# ATMEGA32u4_Breakout_rev1.net
KiCad netlist of a schematic drawn in EAGLE
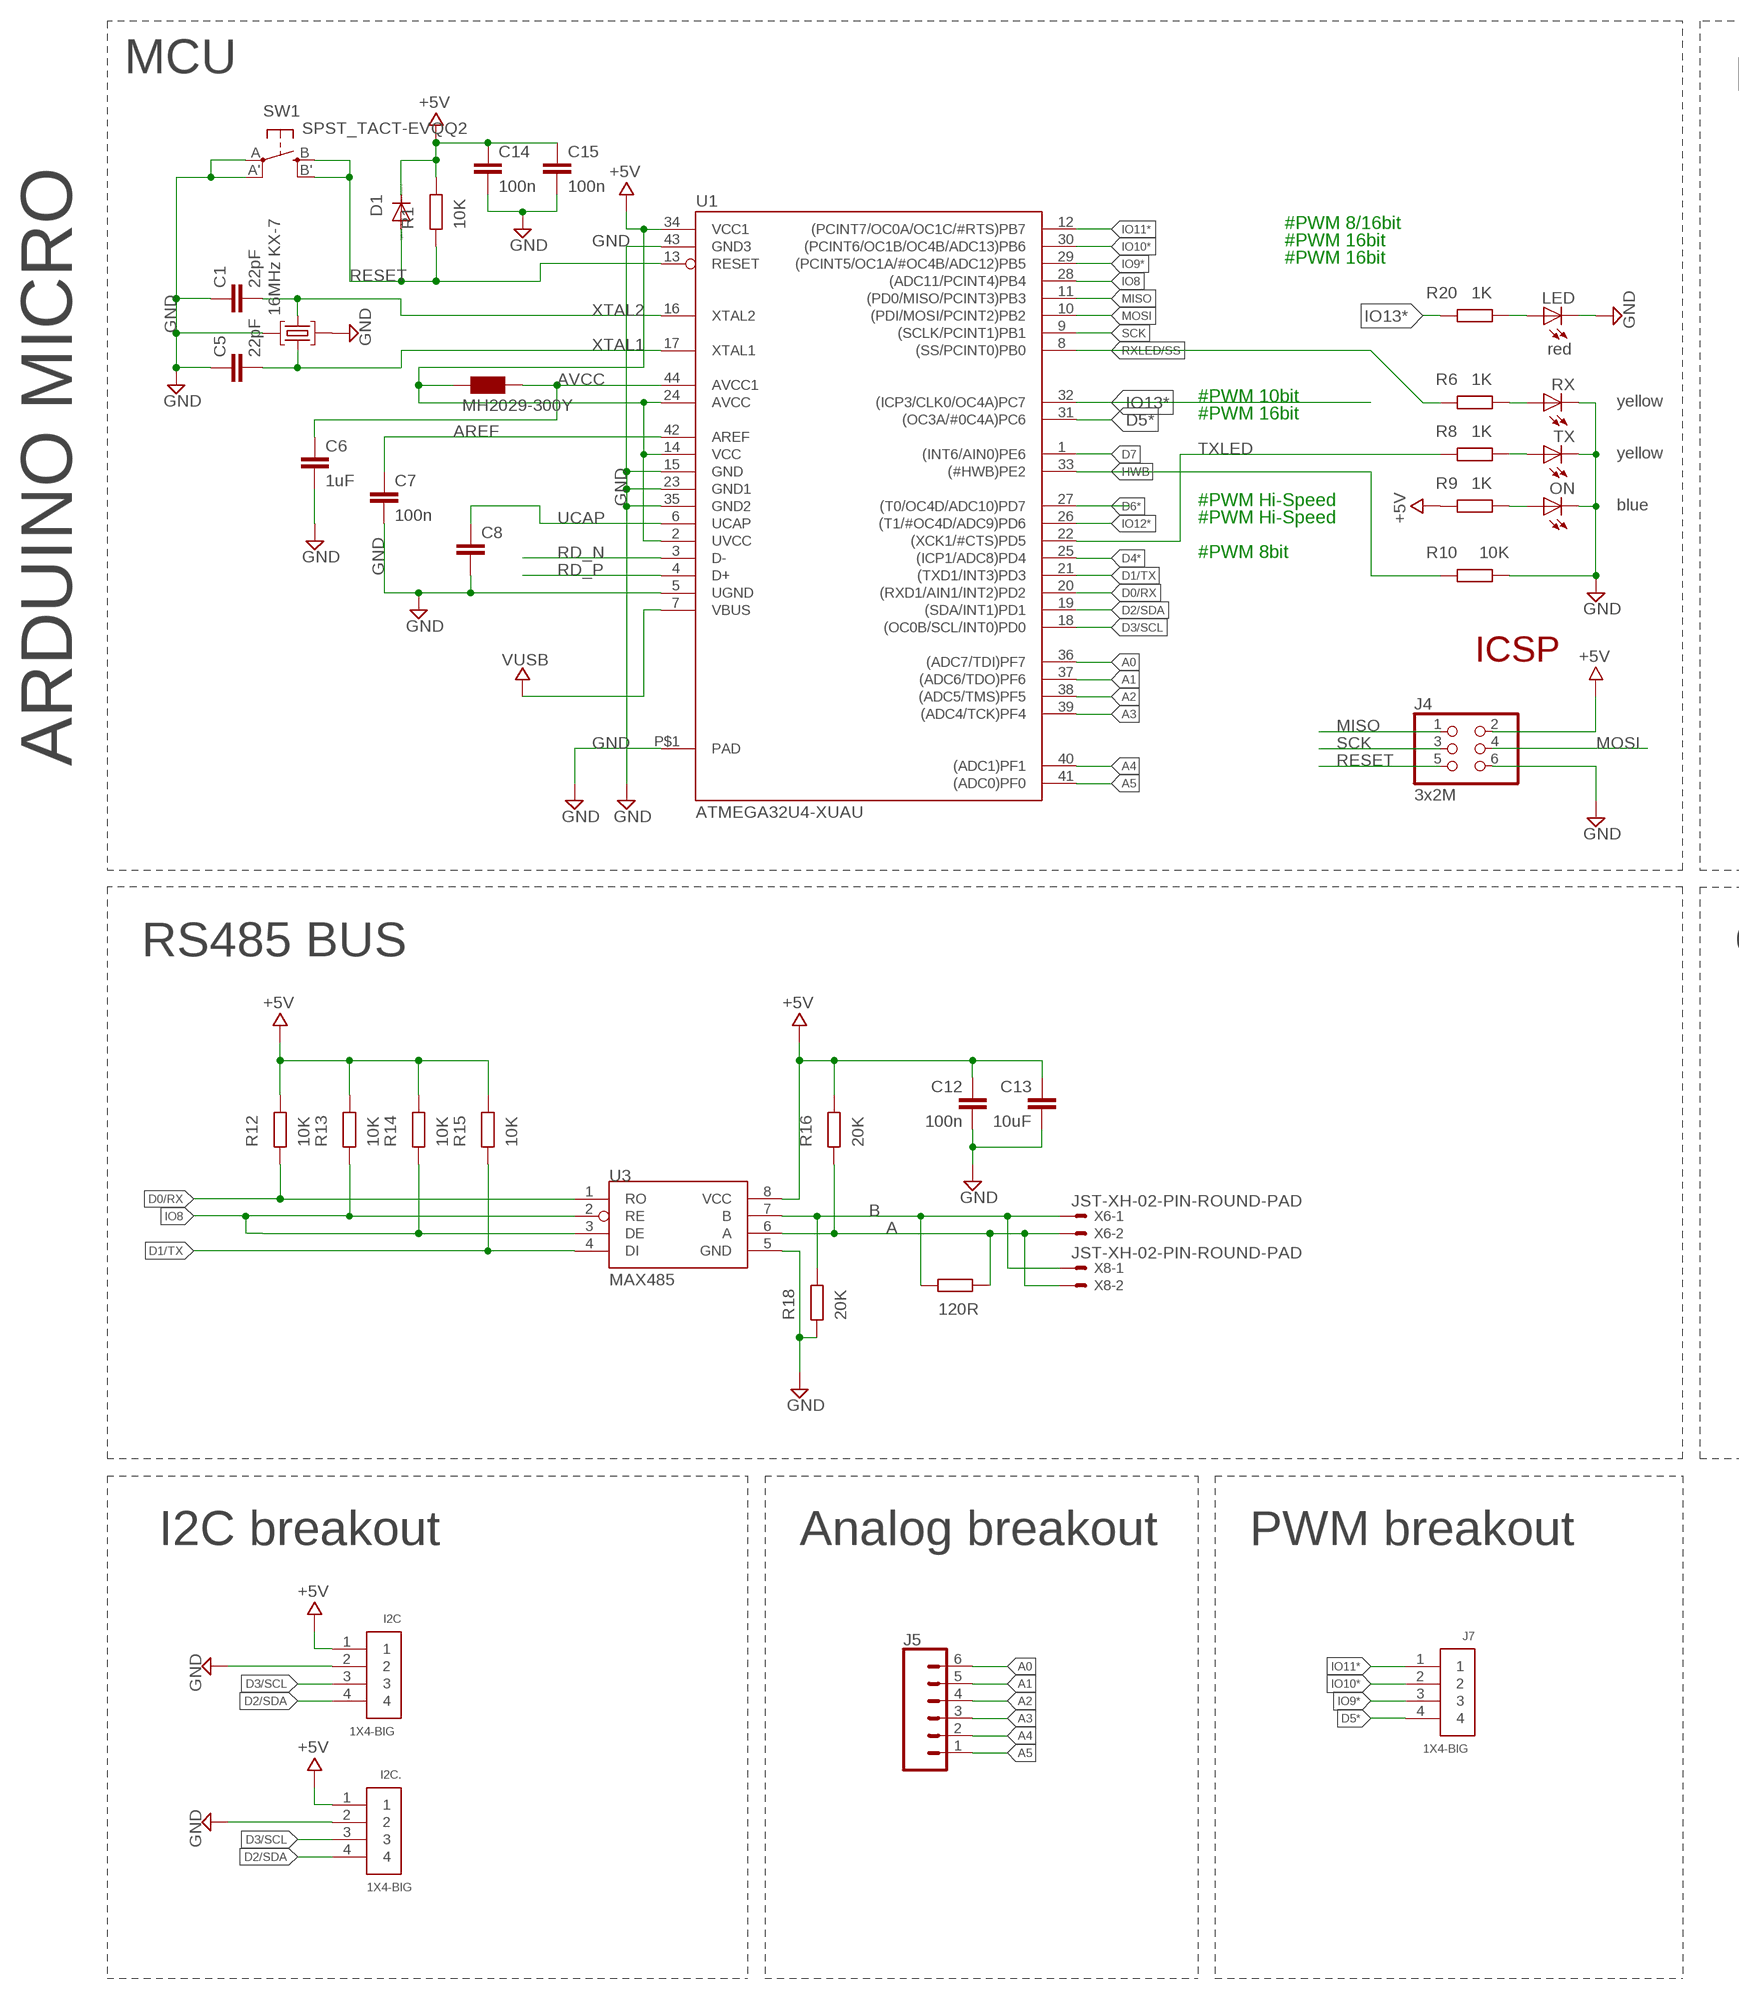
[diagram p0: schematic, sheet 1, part 1 of 2]
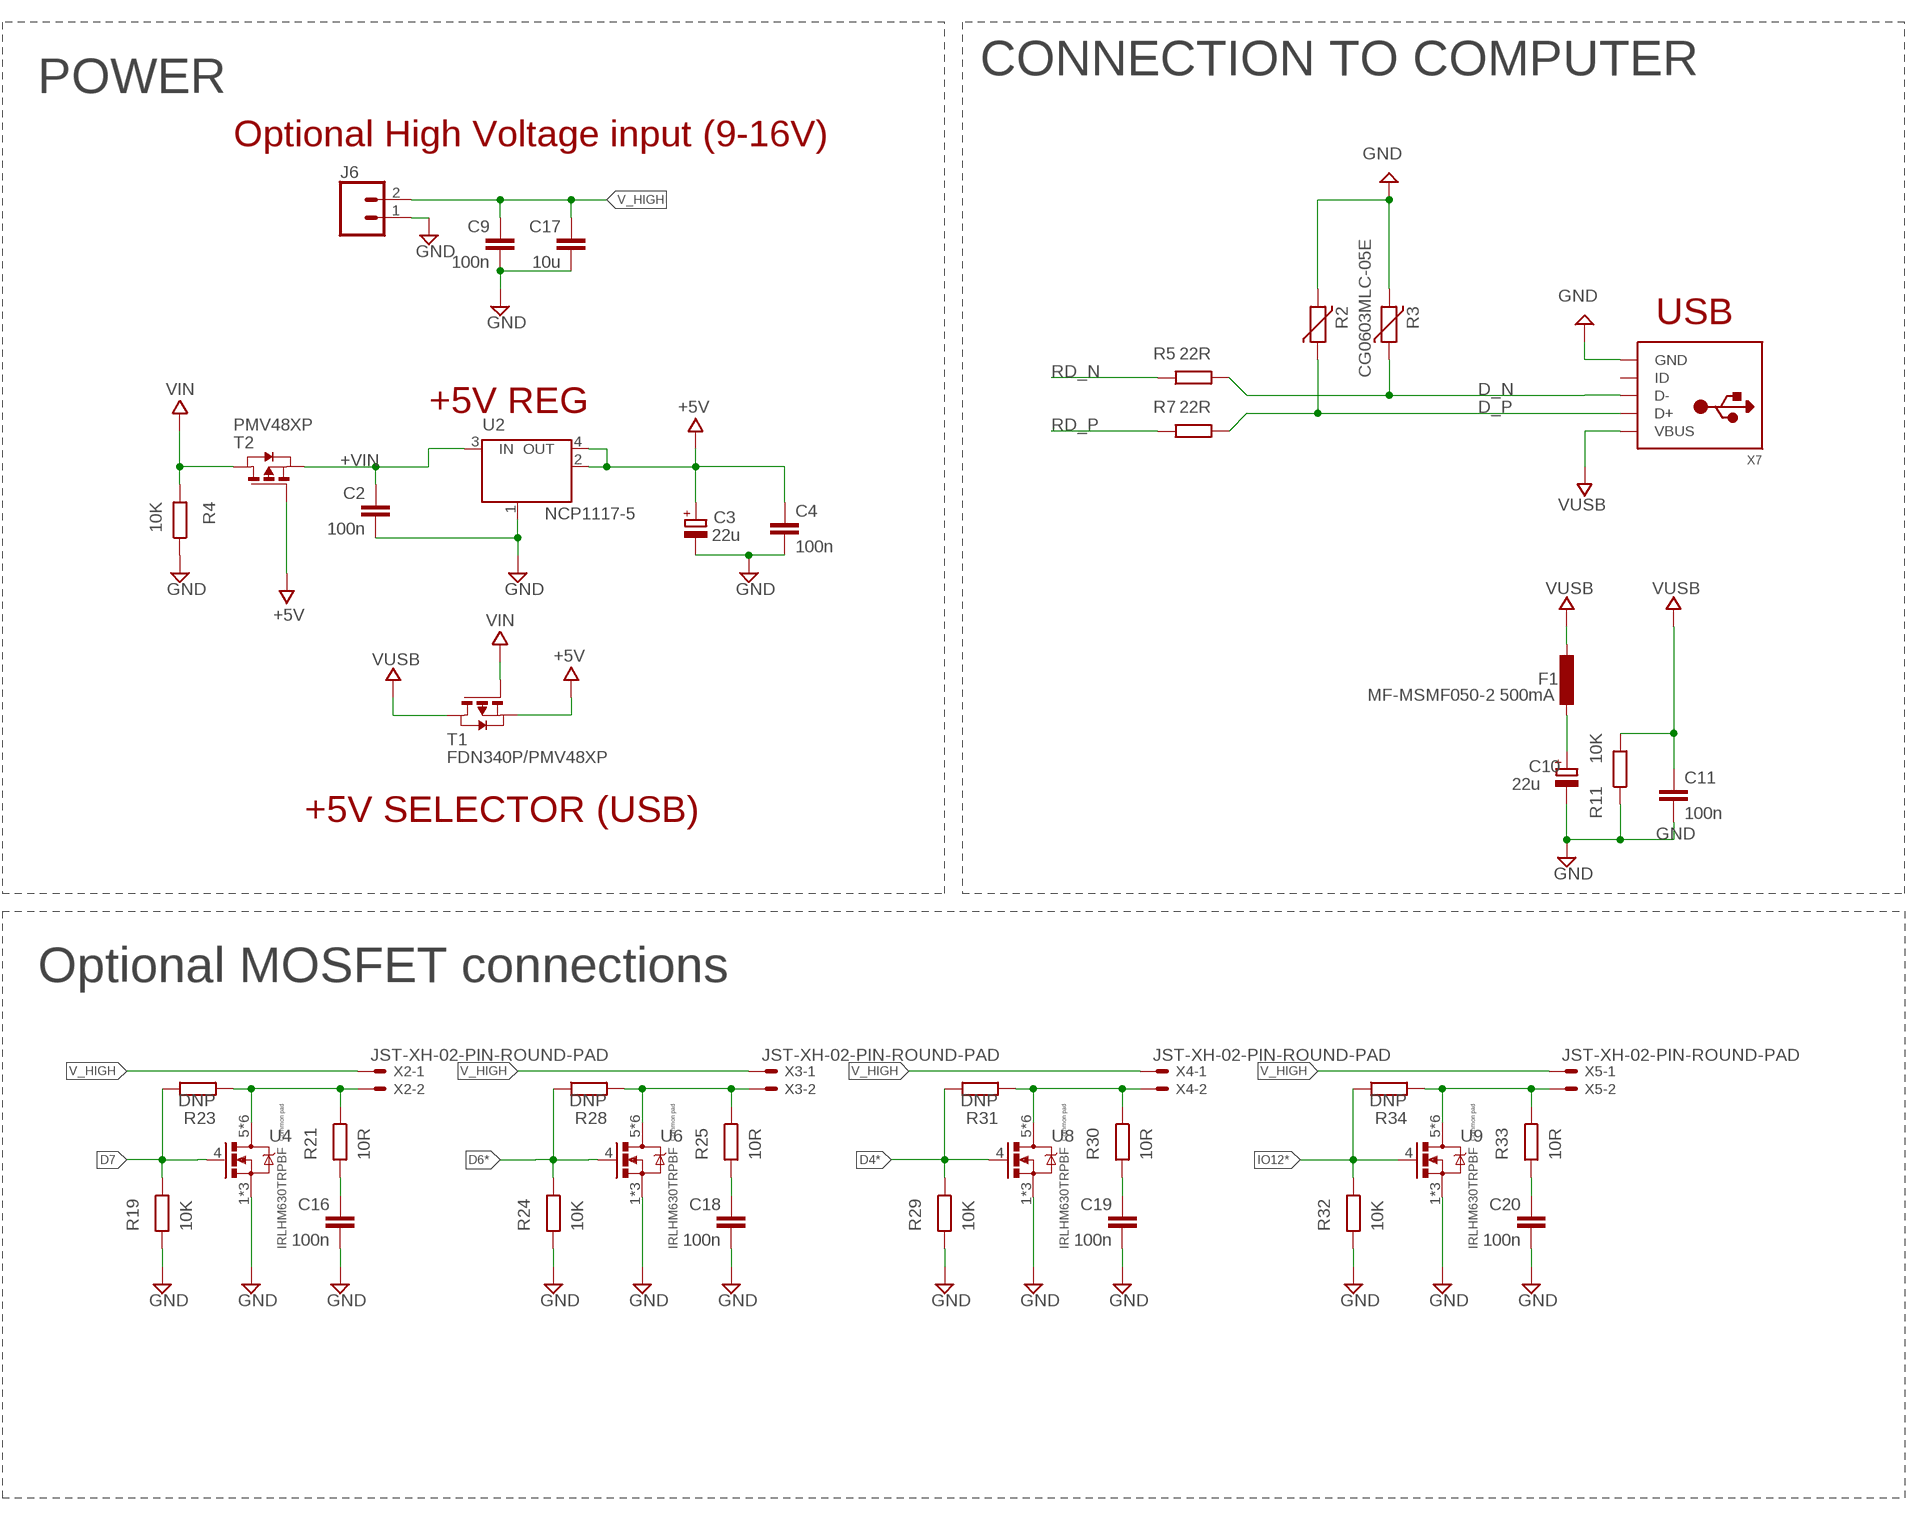
[diagram p1: schematic, sheet 1, part 2 of 2]

(export (version "E")
  (design (tool "Eeschema 10.0.6"))
  (components
    (comp (ref "C1")
      (value "22pF")
      (footprint "eagle-import:C0603-ROUND")
      (libsource (lib "eagle-import") (part "C-EUC0603"))
    )
    (comp (ref "C2")
      (value "100n")
      (footprint "eagle-import:C0603-ROUND")
      (libsource (lib "eagle-import") (part "C-EUC0603"))
    )
    (comp (ref "C3")
      (value "22u")
      (footprint "eagle-import:SMC_B")
      (libsource (lib "eagle-import") (part "CPOL-EUSMCB"))
    )
    (comp (ref "C4")
      (value "100n")
      (footprint "eagle-import:C0603-ROUND")
      (libsource (lib "eagle-import") (part "C-EUC0603"))
    )
    (comp (ref "C5")
      (value "22pF")
      (footprint "eagle-import:C0603-ROUND")
      (libsource (lib "eagle-import") (part "C-EUC0603"))
    )
    (comp (ref "C6")
      (value "1uF")
      (footprint "eagle-import:C0603-ROUND")
      (libsource (lib "eagle-import") (part "C-EUC0603"))
    )
    (comp (ref "C7")
      (value "100n")
      (footprint "eagle-import:C0603-ROUND")
      (libsource (lib "eagle-import") (part "C-EUC0603"))
    )
    (comp (ref "C8")
      (value "1uF")
      (footprint "eagle-import:C0603-ROUND")
      (libsource (lib "eagle-import") (part "C-EUC0603"))
    )
    (comp (ref "C9")
      (value "100n")
      (footprint "eagle-import:C1206")
      (libsource (lib "eagle-import") (part "C-EUC1206"))
    )
    (comp (ref "C10")
      (value "22u")
      (footprint "eagle-import:SMC_B")
      (libsource (lib "eagle-import") (part "CPOL-EUSMCB"))
    )
    (comp (ref "C11")
      (value "100n")
      (footprint "eagle-import:C0603-ROUND")
      (libsource (lib "eagle-import") (part "C-EUC0603"))
    )
    (comp (ref "C12")
      (value "100n")
      (footprint "eagle-import:C0603-ROUND")
      (libsource (lib "eagle-import") (part "C-EUC0603"))
    )
    (comp (ref "C13")
      (value "10uF")
      (footprint "eagle-import:C0603-ROUND")
      (libsource (lib "eagle-import") (part "C-EUC0603"))
    )
    (comp (ref "C14")
      (value "100n")
      (footprint "eagle-import:C0603-ROUND")
      (libsource (lib "eagle-import") (part "C-EUC0603"))
    )
    (comp (ref "C15")
      (value "100n")
      (footprint "eagle-import:C0603-ROUND")
      (libsource (lib "eagle-import") (part "C-EUC0603"))
    )
    (comp (ref "C16")
      (value "100n")
      (footprint "eagle-import:C0603-ROUND")
      (libsource (lib "eagle-import") (part "C-EUC0603"))
    )
    (comp (ref "C17")
      (value "10u")
      (footprint "eagle-import:C1206")
      (libsource (lib "eagle-import") (part "C-EUC1206"))
    )
    (comp (ref "C18")
      (value "100n")
      (footprint "eagle-import:C0603-ROUND")
      (libsource (lib "eagle-import") (part "C-EUC0603"))
    )
    (comp (ref "C19")
      (value "100n")
      (footprint "eagle-import:C0603-ROUND")
      (libsource (lib "eagle-import") (part "C-EUC0603"))
    )
    (comp (ref "C20")
      (value "100n")
      (footprint "eagle-import:C0603-ROUND")
      (libsource (lib "eagle-import") (part "C-EUC0603"))
    )
    (comp (ref "D1")
      (value "CD1206-S01575")
      (footprint "eagle-import:MINIMELF")
      (libsource (lib "eagle-import") (part "DIODE-MINIMELF"))
    )
    (comp (ref "F1")
      (value "MF-MSMF050-2 500mA")
      (footprint "eagle-import:L1812")
      (libsource (lib "eagle-import") (part "L-EUL1812"))
    )
    (comp (ref "I2C")
      (value "1X4-BIG")
      (footprint "eagle-import:1X04-BIG")
      (libsource (lib "eagle-import") (part "1X4-BIG"))
    )
    (comp (ref "I2C.")
      (value "1X4-BIG")
      (footprint "eagle-import:1X04-BIG")
      (libsource (lib "eagle-import") (part "1X4-BIG"))
    )
    (comp (ref "J4")
      (value "3x2M")
      (footprint "eagle-import:2X03")
      (libsource (lib "eagle-import") (part "PINHD-2X3"))
    )
    (comp (ref "J5")
      (value "CONN_06SILK_FEMALE_PTH")
      (footprint "eagle-import:1X06")
      (libsource (lib "eagle-import") (part "CONN_06SILK_FEMALE_PTH"))
    )
    (comp (ref "J6")
      (value "CONN_023.5MM")
      (footprint "eagle-import:SCREWTERMINAL-3.5MM-2")
      (libsource (lib "eagle-import") (part "CONN_023.5MM"))
    )
    (comp (ref "J7")
      (value "1X4-BIG")
      (footprint "eagle-import:1X04-BIG")
      (libsource (lib "eagle-import") (part "1X4-BIG"))
    )
    (comp (ref "L2")
      (value "MH2029-300Y")
      (footprint "eagle-import:0805")
      (libsource (lib "eagle-import") (part "WE-CBF_0805"))
    )
    (comp (ref "LED")
      (value "red")
      (footprint "eagle-import:CHIPLED_0805")
      (libsource (lib "eagle-import") (part "LEDCHIPLED_0805"))
    )
    (comp (ref "ON")
      (value "blue")
      (footprint "eagle-import:CHIPLED_0805")
      (libsource (lib "eagle-import") (part "LEDCHIPLED_0805"))
    )
    (comp (ref "R1")
      (value "10K")
      (footprint "eagle-import:R0603-ROUND")
      (libsource (lib "eagle-import") (part "R-EU_R0603"))
    )
    (comp (ref "R2")
      (value "CG0603MLC-05E")
      (footprint "eagle-import:CT_CN0603")
      (libsource (lib "eagle-import") (part "VARISTORCN0603"))
    )
    (comp (ref "R3")
      (value "CG0603MLC-05E")
      (footprint "eagle-import:CT_CN0603")
      (libsource (lib "eagle-import") (part "VARISTORCN0603"))
    )
    (comp (ref "R4")
      (value "10K")
      (footprint "eagle-import:R0603-ROUND")
      (libsource (lib "eagle-import") (part "R-EU_R0603"))
    )
    (comp (ref "R5")
      (value "22R")
      (footprint "eagle-import:R0603-ROUND")
      (libsource (lib "eagle-import") (part "R-EU_R0603"))
    )
    (comp (ref "R6")
      (value "1K")
      (footprint "eagle-import:R0603-ROUND")
      (libsource (lib "eagle-import") (part "R-EU_R0603"))
    )
    (comp (ref "R7")
      (value "22R")
      (footprint "eagle-import:R0603-ROUND")
      (libsource (lib "eagle-import") (part "R-EU_R0603"))
    )
    (comp (ref "R8")
      (value "1K")
      (footprint "eagle-import:R0603-ROUND")
      (libsource (lib "eagle-import") (part "R-EU_R0603"))
    )
    (comp (ref "R9")
      (value "1K")
      (footprint "eagle-import:R0603-ROUND")
      (libsource (lib "eagle-import") (part "R-EU_R0603"))
    )
    (comp (ref "R10")
      (value "10K")
      (footprint "eagle-import:R0603-ROUND")
      (libsource (lib "eagle-import") (part "R-EU_R0603"))
    )
    (comp (ref "R11")
      (value "10K")
      (footprint "eagle-import:R0603-ROUND")
      (libsource (lib "eagle-import") (part "R-EU_R0603"))
    )
    (comp (ref "R12")
      (value "10K")
      (footprint "eagle-import:R0603-ROUND")
      (libsource (lib "eagle-import") (part "R-EU_R0603"))
    )
    (comp (ref "R13")
      (value "10K")
      (footprint "eagle-import:R0603-ROUND")
      (libsource (lib "eagle-import") (part "R-EU_R0603"))
    )
    (comp (ref "R14")
      (value "10K")
      (footprint "eagle-import:R0603-ROUND")
      (libsource (lib "eagle-import") (part "R-EU_R0603"))
    )
    (comp (ref "R15")
      (value "10K")
      (footprint "eagle-import:R0603-ROUND")
      (libsource (lib "eagle-import") (part "R-EU_R0603"))
    )
    (comp (ref "R16")
      (value "20K")
      (footprint "eagle-import:R0603-ROUND")
      (libsource (lib "eagle-import") (part "R-EU_R0603"))
    )
    (comp (ref "R17")
      (value "120R")
      (footprint "eagle-import:R0603-ROUND")
      (libsource (lib "eagle-import") (part "R-EU_R0603"))
    )
    (comp (ref "R18")
      (value "20K")
      (footprint "eagle-import:R0603-ROUND")
      (libsource (lib "eagle-import") (part "R-EU_R0603"))
    )
    (comp (ref "R19")
      (value "10K")
      (footprint "eagle-import:R0603-ROUND")
      (libsource (lib "eagle-import") (part "R-EU_R0603"))
    )
    (comp (ref "R20")
      (value "1K")
      (footprint "eagle-import:R0603-ROUND")
      (libsource (lib "eagle-import") (part "R-EU_R0603"))
    )
    (comp (ref "R21")
      (value "10R")
      (footprint "eagle-import:R0603-ROUND")
      (libsource (lib "eagle-import") (part "R-EU_R0603"))
    )
    (comp (ref "R23")
      (value "DNP")
      (footprint "eagle-import:R0603-ROUND")
      (libsource (lib "eagle-import") (part "R-EU_R0603"))
    )
    (comp (ref "R24")
      (value "10K")
      (footprint "eagle-import:R0603-ROUND")
      (libsource (lib "eagle-import") (part "R-EU_R0603"))
    )
    (comp (ref "R25")
      (value "10R")
      (footprint "eagle-import:R0603-ROUND")
      (libsource (lib "eagle-import") (part "R-EU_R0603"))
    )
    (comp (ref "R28")
      (value "DNP")
      (footprint "eagle-import:R0603-ROUND")
      (libsource (lib "eagle-import") (part "R-EU_R0603"))
    )
    (comp (ref "R29")
      (value "10K")
      (footprint "eagle-import:R0603-ROUND")
      (libsource (lib "eagle-import") (part "R-EU_R0603"))
    )
    (comp (ref "R30")
      (value "10R")
      (footprint "eagle-import:R0603-ROUND")
      (libsource (lib "eagle-import") (part "R-EU_R0603"))
    )
    (comp (ref "R31")
      (value "DNP")
      (footprint "eagle-import:R0603-ROUND")
      (libsource (lib "eagle-import") (part "R-EU_R0603"))
    )
    (comp (ref "R32")
      (value "10K")
      (footprint "eagle-import:R0603-ROUND")
      (libsource (lib "eagle-import") (part "R-EU_R0603"))
    )
    (comp (ref "R33")
      (value "10R")
      (footprint "eagle-import:R0603-ROUND")
      (libsource (lib "eagle-import") (part "R-EU_R0603"))
    )
    (comp (ref "R34")
      (value "DNP")
      (footprint "eagle-import:R0603-ROUND")
      (libsource (lib "eagle-import") (part "R-EU_R0603"))
    )
    (comp (ref "RX")
      (value "yellow")
      (footprint "eagle-import:CHIPLED_0805")
      (libsource (lib "eagle-import") (part "LEDCHIPLED_0805"))
    )
    (comp (ref "SW1")
      (value "SPST_TACT-EVQQ2")
      (footprint "eagle-import:EVQ-Q2")
      (libsource (lib "eagle-import") (part "SPST_TACT-EVQQ2"))
    )
    (comp (ref "T1")
      (value "FDN340P/PMV48XP")
      (footprint "eagle-import:SOT-23")
      (libsource (lib "eagle-import") (part "PMOSSOT23"))
    )
    (comp (ref "T2")
      (value "PMV48XP")
      (footprint "eagle-import:SOT-23")
      (libsource (lib "eagle-import") (part "PMOSSOT23"))
    )
    (comp (ref "TX")
      (value "yellow")
      (footprint "eagle-import:CHIPLED_0805")
      (libsource (lib "eagle-import") (part "LEDCHIPLED_0805"))
    )
    (comp (ref "U1")
      (value "ATMEGA32U4-XUAU")
      (footprint "eagle-import:TQFP44-PAD")
      (libsource (lib "eagle-import") (part "ATMEGA32U4-XUAU"))
    )
    (comp (ref "U2")
      (value "NCP1117-5")
      (footprint "eagle-import:SOT223")
      (libsource (lib "eagle-import") (part "LINEAR_MC33269ST"))
    )
    (comp (ref "U3")
      (value "MAX485")
      (footprint "eagle-import:SO08")
      (fields (field (name "MF") "Maxim Integrated"))
      (libsource (lib "eagle-import") (part "MAX485"))
    )
    (comp (ref "U4")
      (value "IRLHM630TRPBF")
      (footprint "eagle-import:IRLHM630TRPBF")
      (libsource (lib "eagle-import") (part "IRLHM630TRPBF"))
    )
    (comp (ref "U6")
      (value "IRLHM630TRPBF")
      (footprint "eagle-import:IRLHM630TRPBF")
      (libsource (lib "eagle-import") (part "IRLHM630TRPBF"))
    )
    (comp (ref "U8")
      (value "IRLHM630TRPBF")
      (footprint "eagle-import:IRLHM630TRPBF")
      (libsource (lib "eagle-import") (part "IRLHM630TRPBF"))
    )
    (comp (ref "U9")
      (value "IRLHM630TRPBF")
      (footprint "eagle-import:IRLHM630TRPBF")
      (libsource (lib "eagle-import") (part "IRLHM630TRPBF"))
    )
    (comp (ref "X1")
      (value "16MHz KX-7")
      (footprint "eagle-import:CRYSTAL-3.2-2.5")
      (libsource (lib "eagle-import") (part "CRYSTAL-3.2-2.5"))
    )
    (comp (ref "X2")
      (value "JST-XH-02-PIN-ROUND-PAD")
      (footprint "eagle-import:JST-XH-02-PACKAGE-ROUND-PAD")
      (libsource (lib "eagle-import") (part "JST-XH-02-PIN-ROUND-PAD"))
    )
    (comp (ref "X3")
      (value "JST-XH-02-PIN-ROUND-PAD")
      (footprint "eagle-import:JST-XH-02-PACKAGE-ROUND-PAD")
      (libsource (lib "eagle-import") (part "JST-XH-02-PIN-ROUND-PAD"))
    )
    (comp (ref "X4")
      (value "JST-XH-02-PIN-ROUND-PAD")
      (footprint "eagle-import:JST-XH-02-PACKAGE-ROUND-PAD")
      (libsource (lib "eagle-import") (part "JST-XH-02-PIN-ROUND-PAD"))
    )
    (comp (ref "X5")
      (value "JST-XH-02-PIN-ROUND-PAD")
      (footprint "eagle-import:JST-XH-02-PACKAGE-ROUND-PAD")
      (libsource (lib "eagle-import") (part "JST-XH-02-PIN-ROUND-PAD"))
    )
    (comp (ref "X6")
      (value "JST-XH-02-PIN-ROUND-PAD")
      (footprint "eagle-import:JST-XH-02-PACKAGE-ROUND-PAD")
      (libsource (lib "eagle-import") (part "JST-XH-02-PIN-ROUND-PAD"))
    )
    (comp (ref "X7")
      (value "MICROBUILDER_USB_MICRO_20329_V2")
      (footprint "eagle-import:MICROBUILDER_4UCONN_20329_V2")
      (libsource (lib "eagle-import") (part "MICROBUILDER_USB_MICRO_20329_V2"))
    )
    (comp (ref "X8")
      (value "JST-XH-02-PIN-ROUND-PAD")
      (footprint "eagle-import:JST-XH-02-PACKAGE-ROUND-PAD")
      (libsource (lib "eagle-import") (part "JST-XH-02-PIN-ROUND-PAD"))
    )
  )
  (nets
    (net (code "1") (name "+5V") (class "Default")
      (node (ref "C12") (pin "1") (pinfunction "1_1") (pintype "passive"))
      (node (ref "C13") (pin "1") (pinfunction "1_1") (pintype "passive"))
      (node (ref "C14") (pin "1") (pinfunction "1_1") (pintype "passive"))
      (node (ref "C15") (pin "1") (pinfunction "1_1") (pintype "passive"))
      (node (ref "C3") (pin "+") (pinfunction "+_+") (pintype "passive"))
      (node (ref "C4") (pin "1") (pinfunction "1_1") (pintype "passive"))
      (node (ref "D1") (pin "C") (pinfunction "C_C") (pintype "passive"))
      (node (ref "I2C") (pin "1") (pinfunction "1_1") (pintype "bidirectional"))
      (node (ref "I2C.") (pin "1") (pinfunction "1_1") (pintype "bidirectional"))
      (node (ref "J4") (pin "2") (pinfunction "2_2") (pintype "passive"))
      (node (ref "L2") (pin "1") (pinfunction "1_1") (pintype "passive"))
      (node (ref "R1") (pin "1") (pinfunction "1_1") (pintype "passive"))
      (node (ref "R12") (pin "1") (pinfunction "1_1") (pintype "passive"))
      (node (ref "R13") (pin "1") (pinfunction "1_1") (pintype "passive"))
      (node (ref "R14") (pin "1") (pinfunction "1_1") (pintype "passive"))
      (node (ref "R15") (pin "1") (pinfunction "1_1") (pintype "passive"))
      (node (ref "R16") (pin "1") (pinfunction "1_1") (pintype "passive"))
      (node (ref "R9") (pin "1") (pinfunction "1_1") (pintype "passive"))
      (node (ref "T1") (pin "2") (pinfunction "S_2") (pintype "passive"))
      (node (ref "T2") (pin "3") (pinfunction "G_3") (pintype "passive"))
      (node (ref "U1") (pin "14") (pinfunction "VCC_14") (pintype "power_in"))
      (node (ref "U1") (pin "2") (pinfunction "UVCC_2") (pintype "power_in"))
      (node (ref "U1") (pin "24") (pinfunction "AVCC_24") (pintype "power_in"))
      (node (ref "U1") (pin "34") (pinfunction "VCC1_34") (pintype "power_in"))
      (node (ref "U2") (pin "2") (pinfunction "OUT_2") (pintype "passive"))
      (node (ref "U2") (pin "4") (pinfunction "OUT_4") (pintype "passive"))
      (node (ref "U3") (pin "8") (pinfunction "VCC_8") (pintype "bidirectional"))
    )
    (net (code "2") (name "/+VIN") (class "Default")
      (node (ref "C2") (pin "1") (pinfunction "1_1") (pintype "passive"))
      (node (ref "T2") (pin "2") (pinfunction "S_2") (pintype "passive"))
      (node (ref "U2") (pin "3") (pinfunction "IN_3") (pintype "input"))
    )
    (net (code "3") (name "/A") (class "Default")
      (node (ref "R16") (pin "2") (pinfunction "2_2") (pintype "passive"))
      (node (ref "R17") (pin "1") (pinfunction "1_1") (pintype "passive"))
      (node (ref "U3") (pin "6") (pinfunction "A_6") (pintype "bidirectional"))
      (node (ref "X6") (pin "2") (pinfunction "S_2") (pintype "passive"))
      (node (ref "X8") (pin "2") (pinfunction "S_2") (pintype "passive"))
    )
    (net (code "4") (name "/AREF") (class "Default")
      (node (ref "C7") (pin "1") (pinfunction "1_1") (pintype "passive"))
      (node (ref "U1") (pin "42") (pinfunction "AREF_42") (pintype "power_in"))
    )
    (net (code "5") (name "/AVCC") (class "Default")
      (node (ref "C6") (pin "1") (pinfunction "1_1") (pintype "passive"))
      (node (ref "L2") (pin "2") (pinfunction "2_2") (pintype "passive"))
      (node (ref "U1") (pin "44") (pinfunction "AVCC1_44") (pintype "power_in"))
    )
    (net (code "6") (name "/B") (class "Default")
      (node (ref "R17") (pin "2") (pinfunction "2_2") (pintype "passive"))
      (node (ref "R18") (pin "1") (pinfunction "1_1") (pintype "passive"))
      (node (ref "U3") (pin "7") (pinfunction "B_7") (pintype "bidirectional"))
      (node (ref "X6") (pin "1") (pinfunction "S_1") (pintype "passive"))
      (node (ref "X8") (pin "1") (pinfunction "S_1") (pintype "passive"))
    )
    (net (code "7") (name "/D_N") (class "Default")
      (node (ref "R3") (pin "1") (pinfunction "1_1") (pintype "passive"))
      (node (ref "R5") (pin "2") (pinfunction "2_2") (pintype "passive"))
      (node (ref "X7") (pin "D-") (pinfunction "D-_D-") (pintype "bidirectional"))
    )
    (net (code "8") (name "/D_P") (class "Default")
      (node (ref "R2") (pin "1") (pinfunction "1_1") (pintype "passive"))
      (node (ref "R7") (pin "2") (pinfunction "2_2") (pintype "passive"))
      (node (ref "X7") (pin "D+") (pinfunction "D+_D+") (pintype "bidirectional"))
    )
    (net (code "9") (name "/RD_N") (class "Default")
      (node (ref "R5") (pin "1") (pinfunction "1_1") (pintype "passive"))
      (node (ref "U1") (pin "3") (pinfunction "D-_3") (pintype "bidirectional"))
    )
    (net (code "10") (name "/RD_P") (class "Default")
      (node (ref "R7") (pin "1") (pinfunction "1_1") (pintype "passive"))
      (node (ref "U1") (pin "4") (pinfunction "D+_4") (pintype "bidirectional"))
    )
    (net (code "11") (name "/RESET") (class "Default")
      (node (ref "D1") (pin "A") (pinfunction "A_A") (pintype "passive"))
      (node (ref "J4") (pin "5") (pinfunction "5_5") (pintype "passive"))
      (node (ref "R1") (pin "2") (pinfunction "2_2") (pintype "passive"))
      (node (ref "SW1") (pin "B") (pinfunction "S_B") (pintype "passive"))
      (node (ref "SW1") (pin "B'") (pinfunction "S1_B'") (pintype "passive"))
      (node (ref "U1") (pin "13") (pinfunction "RESET_13") (pintype "input"))
    )
    (net (code "12") (name "/TXLED") (class "Default")
      (node (ref "R8") (pin "1") (pinfunction "1_1") (pintype "passive"))
      (node (ref "U1") (pin "22") (pinfunction "(XCK1/#CTS)PD5_22") (pintype "bidirectional"))
    )
    (net (code "13") (name "/UCAP") (class "Default")
      (node (ref "C8") (pin "1") (pinfunction "1_1") (pintype "passive"))
      (node (ref "U1") (pin "6") (pinfunction "UCAP_6") (pintype "passive"))
    )
    (net (code "14") (name "/XTAL1") (class "Default")
      (node (ref "C5") (pin "2") (pinfunction "2_2") (pintype "passive"))
      (node (ref "U1") (pin "17") (pinfunction "XTAL1_17") (pintype "bidirectional"))
      (node (ref "X1") (pin "3") (pinfunction "C2_3") (pintype "passive"))
    )
    (net (code "15") (name "/XTAL2") (class "Default")
      (node (ref "C1") (pin "2") (pinfunction "2_2") (pintype "passive"))
      (node (ref "U1") (pin "16") (pinfunction "XTAL2_16") (pintype "bidirectional"))
      (node (ref "X1") (pin "1") (pinfunction "C1_1") (pintype "passive"))
    )
    (net (code "16") (name "A0") (class "Default")
      (node (ref "J5") (pin "6") (pinfunction "6_6") (pintype "passive"))
      (node (ref "U1") (pin "36") (pinfunction "(ADC7/TDI)PF7_36") (pintype "bidirectional"))
    )
    (net (code "17") (name "A1") (class "Default")
      (node (ref "J5") (pin "5") (pinfunction "5_5") (pintype "passive"))
      (node (ref "U1") (pin "37") (pinfunction "(ADC6/TDO)PF6_37") (pintype "bidirectional"))
    )
    (net (code "18") (name "A2") (class "Default")
      (node (ref "J5") (pin "4") (pinfunction "4_4") (pintype "passive"))
      (node (ref "U1") (pin "38") (pinfunction "(ADC5/TMS)PF5_38") (pintype "bidirectional"))
    )
    (net (code "19") (name "A3") (class "Default")
      (node (ref "J5") (pin "3") (pinfunction "3_3") (pintype "passive"))
      (node (ref "U1") (pin "39") (pinfunction "(ADC4/TCK)PF4_39") (pintype "bidirectional"))
    )
    (net (code "20") (name "A4") (class "Default")
      (node (ref "J5") (pin "2") (pinfunction "2_2") (pintype "passive"))
      (node (ref "U1") (pin "40") (pinfunction "(ADC1)PF1_40") (pintype "bidirectional"))
    )
    (net (code "21") (name "A5") (class "Default")
      (node (ref "J5") (pin "1") (pinfunction "1_1") (pintype "passive"))
      (node (ref "U1") (pin "41") (pinfunction "(ADC0)PF0_41") (pintype "bidirectional"))
    )
    (net (code "22") (name "D0{slash}RX") (class "Default")
      (node (ref "R12") (pin "2") (pinfunction "2_2") (pintype "passive"))
      (node (ref "U1") (pin "20") (pinfunction "(RXD1/AIN1/INT2)PD2_20") (pintype "bidirectional"))
      (node (ref "U3") (pin "1") (pinfunction "RO_1") (pintype "bidirectional"))
    )
    (net (code "23") (name "D1{slash}TX") (class "Default")
      (node (ref "R15") (pin "2") (pinfunction "2_2") (pintype "passive"))
      (node (ref "U1") (pin "21") (pinfunction "(TXD1/INT3)PD3_21") (pintype "bidirectional"))
      (node (ref "U3") (pin "4") (pinfunction "DI_4") (pintype "bidirectional"))
    )
    (net (code "24") (name "D2{slash}SDA") (class "Default")
      (node (ref "I2C") (pin "4") (pinfunction "4_4") (pintype "bidirectional"))
      (node (ref "I2C.") (pin "4") (pinfunction "4_4") (pintype "bidirectional"))
      (node (ref "U1") (pin "19") (pinfunction "(SDA/INT1)PD1_19") (pintype "bidirectional"))
    )
    (net (code "25") (name "D3{slash}SCL") (class "Default")
      (node (ref "I2C") (pin "3") (pinfunction "3_3") (pintype "bidirectional"))
      (node (ref "I2C.") (pin "3") (pinfunction "3_3") (pintype "bidirectional"))
      (node (ref "U1") (pin "18") (pinfunction "(OC0B/SCL/INT0)PD0_18") (pintype "bidirectional"))
    )
    (net (code "26") (name "D4*") (class "Default")
      (node (ref "R29") (pin "1") (pinfunction "1_1") (pintype "passive"))
      (node (ref "R31") (pin "1") (pinfunction "1_1") (pintype "passive"))
      (node (ref "U1") (pin "25") (pinfunction "(ICP1/ADC8)PD4_25") (pintype "bidirectional"))
      (node (ref "U8") (pin "4") (pinfunction "4_4") (pintype "bidirectional"))
    )
    (net (code "27") (name "D5*") (class "Default")
      (node (ref "J7") (pin "4") (pinfunction "4_4") (pintype "bidirectional"))
      (node (ref "U1") (pin "31") (pinfunction "(OC3A/#0C4A)PC6_31") (pintype "bidirectional"))
    )
    (net (code "28") (name "D6*") (class "Default")
      (node (ref "R24") (pin "1") (pinfunction "1_1") (pintype "passive"))
      (node (ref "R28") (pin "1") (pinfunction "1_1") (pintype "passive"))
      (node (ref "U1") (pin "27") (pinfunction "(T0/OC4D/ADC10)PD7_27") (pintype "bidirectional"))
      (node (ref "U6") (pin "4") (pinfunction "4_4") (pintype "bidirectional"))
    )
    (net (code "29") (name "D7") (class "Default")
      (node (ref "R19") (pin "1") (pinfunction "1_1") (pintype "passive"))
      (node (ref "R23") (pin "1") (pinfunction "1_1") (pintype "passive"))
      (node (ref "U1") (pin "1") (pinfunction "(INT6/AIN0)PE6_1") (pintype "bidirectional"))
      (node (ref "U4") (pin "4") (pinfunction "4_4") (pintype "bidirectional"))
    )
    (net (code "30") (name "GND") (class "Default")
      (node (ref "C1") (pin "1") (pinfunction "1_1") (pintype "passive"))
      (node (ref "C10") (pin "-") (pinfunction "-_-") (pintype "passive"))
      (node (ref "C11") (pin "2") (pinfunction "2_2") (pintype "passive"))
      (node (ref "C12") (pin "2") (pinfunction "2_2") (pintype "passive"))
      (node (ref "C13") (pin "2") (pinfunction "2_2") (pintype "passive"))
      (node (ref "C14") (pin "2") (pinfunction "2_2") (pintype "passive"))
      (node (ref "C15") (pin "2") (pinfunction "2_2") (pintype "passive"))
      (node (ref "C16") (pin "2") (pinfunction "2_2") (pintype "passive"))
      (node (ref "C17") (pin "2") (pinfunction "2_2") (pintype "passive"))
      (node (ref "C18") (pin "2") (pinfunction "2_2") (pintype "passive"))
      (node (ref "C19") (pin "2") (pinfunction "2_2") (pintype "passive"))
      (node (ref "C2") (pin "2") (pinfunction "2_2") (pintype "passive"))
      (node (ref "C20") (pin "2") (pinfunction "2_2") (pintype "passive"))
      (node (ref "C3") (pin "-") (pinfunction "-_-") (pintype "passive"))
      (node (ref "C4") (pin "2") (pinfunction "2_2") (pintype "passive"))
      (node (ref "C5") (pin "1") (pinfunction "1_1") (pintype "passive"))
      (node (ref "C6") (pin "2") (pinfunction "2_2") (pintype "passive"))
      (node (ref "C7") (pin "2") (pinfunction "2_2") (pintype "passive"))
      (node (ref "C8") (pin "2") (pinfunction "2_2") (pintype "passive"))
      (node (ref "C9") (pin "2") (pinfunction "2_2") (pintype "passive"))
      (node (ref "I2C") (pin "2") (pinfunction "2_2") (pintype "bidirectional"))
      (node (ref "I2C.") (pin "2") (pinfunction "2_2") (pintype "bidirectional"))
      (node (ref "J4") (pin "6") (pinfunction "6_6") (pintype "passive"))
      (node (ref "J6") (pin "1") (pinfunction "1_1") (pintype "passive"))
      (node (ref "LED") (pin "C") (pinfunction "C_C") (pintype "passive"))
      (node (ref "ON") (pin "C") (pinfunction "C_C") (pintype "passive"))
      (node (ref "R10") (pin "2") (pinfunction "2_2") (pintype "passive"))
      (node (ref "R11") (pin "1") (pinfunction "1_1") (pintype "passive"))
      (node (ref "R18") (pin "2") (pinfunction "2_2") (pintype "passive"))
      (node (ref "R19") (pin "2") (pinfunction "2_2") (pintype "passive"))
      (node (ref "R2") (pin "2") (pinfunction "2_2") (pintype "passive"))
      (node (ref "R24") (pin "2") (pinfunction "2_2") (pintype "passive"))
      (node (ref "R29") (pin "2") (pinfunction "2_2") (pintype "passive"))
      (node (ref "R3") (pin "2") (pinfunction "2_2") (pintype "passive"))
      (node (ref "R32") (pin "2") (pinfunction "2_2") (pintype "passive"))
      (node (ref "R4") (pin "1") (pinfunction "1_1") (pintype "passive"))
      (node (ref "RX") (pin "C") (pinfunction "C_C") (pintype "passive"))
      (node (ref "SW1") (pin "A") (pinfunction "P_A") (pintype "passive"))
      (node (ref "SW1") (pin "A'") (pinfunction "P1_A'") (pintype "passive"))
      (node (ref "TX") (pin "C") (pinfunction "C_C") (pintype "passive"))
      (node (ref "U1") (pin "15") (pinfunction "GND_15") (pintype "power_in"))
      (node (ref "U1") (pin "23") (pinfunction "GND1_23") (pintype "power_in"))
      (node (ref "U1") (pin "35") (pinfunction "GND2_35") (pintype "power_in"))
      (node (ref "U1") (pin "43") (pinfunction "GND3_43") (pintype "power_in"))
      (node (ref "U1") (pin "5") (pinfunction "UGND_5") (pintype "power_in"))
      (node (ref "U1") (pin "P$1") (pinfunction "PAD_P$1") (pintype "power_in"))
      (node (ref "U2") (pin "1") (pinfunction "GND/ADJ_1") (pintype "input"))
      (node (ref "U3") (pin "5") (pinfunction "GND_5") (pintype "bidirectional"))
      (node (ref "U4") (pin "1") (pinfunction "1_1") (pintype "bidirectional"))
      (node (ref "U4") (pin "2") (pinfunction "1_2") (pintype "bidirectional"))
      (node (ref "U4") (pin "3") (pinfunction "1_3") (pintype "bidirectional"))
      (node (ref "U6") (pin "1") (pinfunction "1_1") (pintype "bidirectional"))
      (node (ref "U6") (pin "2") (pinfunction "1_2") (pintype "bidirectional"))
      (node (ref "U6") (pin "3") (pinfunction "1_3") (pintype "bidirectional"))
      (node (ref "U8") (pin "1") (pinfunction "1_1") (pintype "bidirectional"))
      (node (ref "U8") (pin "2") (pinfunction "1_2") (pintype "bidirectional"))
      (node (ref "U8") (pin "3") (pinfunction "1_3") (pintype "bidirectional"))
      (node (ref "U9") (pin "1") (pinfunction "1_1") (pintype "bidirectional"))
      (node (ref "U9") (pin "2") (pinfunction "1_2") (pintype "bidirectional"))
      (node (ref "U9") (pin "3") (pinfunction "1_3") (pintype "bidirectional"))
      (node (ref "X1") (pin "2") (pinfunction "GND_2") (pintype "passive"))
      (node (ref "X1") (pin "4") (pinfunction "GND_4") (pintype "passive"))
      (node (ref "X7") (pin "BASE@1") (pinfunction "GND_BASE@1") (pintype "power_in"))
      (node (ref "X7") (pin "BASE@2") (pinfunction "GND_BASE@2") (pintype "power_in"))
      (node (ref "X7") (pin "GND") (pinfunction "GND_GND") (pintype "power_in"))
      (node (ref "X7") (pin "SPRT@1") (pinfunction "GND_SPRT@1") (pintype "power_in"))
      (node (ref "X7") (pin "SPRT@2") (pinfunction "GND_SPRT@2") (pintype "power_in"))
      (node (ref "X7") (pin "SPRT@3") (pinfunction "GND_SPRT@3") (pintype "power_in"))
      (node (ref "X7") (pin "SPRT@4") (pinfunction "GND_SPRT@4") (pintype "power_in"))
    )
    (net (code "31") (name "HWB") (class "Default")
      (node (ref "R10") (pin "1") (pinfunction "1_1") (pintype "passive"))
      (node (ref "U1") (pin "33") (pinfunction "(#HWB)PE2_33") (pintype "bidirectional"))
    )
    (net (code "32") (name "IO8") (class "Default")
      (node (ref "R13") (pin "2") (pinfunction "2_2") (pintype "passive"))
      (node (ref "R14") (pin "2") (pinfunction "2_2") (pintype "passive"))
      (node (ref "U1") (pin "28") (pinfunction "(ADC11/PCINT4)PB4_28") (pintype "bidirectional"))
      (node (ref "U3") (pin "2") (pinfunction "RE_2") (pintype "bidirectional"))
      (node (ref "U3") (pin "3") (pinfunction "DE_3") (pintype "bidirectional"))
    )
    (net (code "33") (name "IO9*") (class "Default")
      (node (ref "J7") (pin "3") (pinfunction "3_3") (pintype "bidirectional"))
      (node (ref "U1") (pin "29") (pinfunction "(PCINT5/OC1A/#OC4B/ADC12)PB5_29") (pintype "bidirectional"))
    )
    (net (code "34") (name "IO10*") (class "Default")
      (node (ref "J7") (pin "2") (pinfunction "2_2") (pintype "bidirectional"))
      (node (ref "U1") (pin "30") (pinfunction "(PCINT6/OC1B/OC4B/ADC13)PB6_30") (pintype "bidirectional"))
    )
    (net (code "35") (name "IO11*") (class "Default")
      (node (ref "J7") (pin "1") (pinfunction "1_1") (pintype "bidirectional"))
      (node (ref "U1") (pin "12") (pinfunction "(PCINT7/OC0A/OC1C/#RTS)PB7_12") (pintype "bidirectional"))
    )
    (net (code "36") (name "IO12*") (class "Default")
      (node (ref "R32") (pin "1") (pinfunction "1_1") (pintype "passive"))
      (node (ref "R34") (pin "1") (pinfunction "1_1") (pintype "passive"))
      (node (ref "U1") (pin "26") (pinfunction "(T1/#OC4D/ADC9)PD6_26") (pintype "bidirectional"))
      (node (ref "U9") (pin "4") (pinfunction "4_4") (pintype "bidirectional"))
    )
    (net (code "37") (name "IO13*") (class "Default")
      (node (ref "R20") (pin "1") (pinfunction "1_1") (pintype "passive"))
      (node (ref "U1") (pin "32") (pinfunction "(ICP3/CLK0/OC4A)PC7_32") (pintype "bidirectional"))
    )
    (net (code "38") (name "MISO") (class "Default")
      (node (ref "J4") (pin "1") (pinfunction "1_1") (pintype "passive"))
      (node (ref "U1") (pin "11") (pinfunction "(PD0/MISO/PCINT3)PB3_11") (pintype "bidirectional"))
    )
    (net (code "39") (name "MOSI") (class "Default")
      (node (ref "J4") (pin "4") (pinfunction "4_4") (pintype "passive"))
      (node (ref "U1") (pin "10") (pinfunction "(PDI/MOSI/PCINT2)PB2_10") (pintype "bidirectional"))
    )
    (net (code "40") (name "Net-(C10-Pad+)") (class "Default")
      (node (ref "C10") (pin "+") (pinfunction "+_+") (pintype "passive"))
      (node (ref "F1") (pin "1") (pinfunction "1_1") (pintype "passive"))
    )
    (net (code "41") (name "Net-(C16-Pad1)") (class "Default")
      (node (ref "C16") (pin "1") (pinfunction "1_1") (pintype "passive"))
      (node (ref "R21") (pin "2") (pinfunction "2_2") (pintype "passive"))
    )
    (net (code "42") (name "Net-(C18-Pad1)") (class "Default")
      (node (ref "C18") (pin "1") (pinfunction "1_1") (pintype "passive"))
      (node (ref "R25") (pin "2") (pinfunction "2_2") (pintype "passive"))
    )
    (net (code "43") (name "Net-(C19-Pad1)") (class "Default")
      (node (ref "C19") (pin "1") (pinfunction "1_1") (pintype "passive"))
      (node (ref "R30") (pin "2") (pinfunction "2_2") (pintype "passive"))
    )
    (net (code "44") (name "Net-(C20-Pad1)") (class "Default")
      (node (ref "C20") (pin "1") (pinfunction "1_1") (pintype "passive"))
      (node (ref "R33") (pin "2") (pinfunction "2_2") (pintype "passive"))
    )
    (net (code "45") (name "Net-(LED-PadA)") (class "Default")
      (node (ref "LED") (pin "A") (pinfunction "A_A") (pintype "passive"))
      (node (ref "R20") (pin "2") (pinfunction "2_2") (pintype "passive"))
    )
    (net (code "46") (name "Net-(ON-PadA)") (class "Default")
      (node (ref "ON") (pin "A") (pinfunction "A_A") (pintype "passive"))
      (node (ref "R9") (pin "2") (pinfunction "2_2") (pintype "passive"))
    )
    (net (code "47") (name "Net-(R6-Pad2)") (class "Default")
      (node (ref "R6") (pin "2") (pinfunction "2_2") (pintype "passive"))
      (node (ref "RX") (pin "A") (pinfunction "A_A") (pintype "passive"))
    )
    (net (code "48") (name "Net-(R8-Pad2)") (class "Default")
      (node (ref "R8") (pin "2") (pinfunction "2_2") (pintype "passive"))
      (node (ref "TX") (pin "A") (pinfunction "A_A") (pintype "passive"))
    )
    (net (code "49") (name "Net-(X2B-S)") (class "Default")
      (node (ref "R21") (pin "1") (pinfunction "1_1") (pintype "passive"))
      (node (ref "R23") (pin "2") (pinfunction "2_2") (pintype "passive"))
      (node (ref "U4") (pin "10") (pinfunction "5_10") (pintype "bidirectional"))
      (node (ref "U4") (pin "5") (pinfunction "5_5") (pintype "bidirectional"))
      (node (ref "U4") (pin "6") (pinfunction "5_6") (pintype "bidirectional"))
      (node (ref "U4") (pin "7") (pinfunction "5_7") (pintype "bidirectional"))
      (node (ref "U4") (pin "8") (pinfunction "5_8") (pintype "bidirectional"))
      (node (ref "U4") (pin "9") (pinfunction "5_9") (pintype "bidirectional"))
      (node (ref "X2") (pin "2") (pinfunction "S_2") (pintype "passive"))
    )
    (net (code "50") (name "Net-(X3B-S)") (class "Default")
      (node (ref "R25") (pin "1") (pinfunction "1_1") (pintype "passive"))
      (node (ref "R28") (pin "2") (pinfunction "2_2") (pintype "passive"))
      (node (ref "U6") (pin "10") (pinfunction "5_10") (pintype "bidirectional"))
      (node (ref "U6") (pin "5") (pinfunction "5_5") (pintype "bidirectional"))
      (node (ref "U6") (pin "6") (pinfunction "5_6") (pintype "bidirectional"))
      (node (ref "U6") (pin "7") (pinfunction "5_7") (pintype "bidirectional"))
      (node (ref "U6") (pin "8") (pinfunction "5_8") (pintype "bidirectional"))
      (node (ref "U6") (pin "9") (pinfunction "5_9") (pintype "bidirectional"))
      (node (ref "X3") (pin "2") (pinfunction "S_2") (pintype "passive"))
    )
    (net (code "51") (name "Net-(X4B-S)") (class "Default")
      (node (ref "R30") (pin "1") (pinfunction "1_1") (pintype "passive"))
      (node (ref "R31") (pin "2") (pinfunction "2_2") (pintype "passive"))
      (node (ref "U8") (pin "10") (pinfunction "5_10") (pintype "bidirectional"))
      (node (ref "U8") (pin "5") (pinfunction "5_5") (pintype "bidirectional"))
      (node (ref "U8") (pin "6") (pinfunction "5_6") (pintype "bidirectional"))
      (node (ref "U8") (pin "7") (pinfunction "5_7") (pintype "bidirectional"))
      (node (ref "U8") (pin "8") (pinfunction "5_8") (pintype "bidirectional"))
      (node (ref "U8") (pin "9") (pinfunction "5_9") (pintype "bidirectional"))
      (node (ref "X4") (pin "2") (pinfunction "S_2") (pintype "passive"))
    )
    (net (code "52") (name "Net-(X5B-S)") (class "Default")
      (node (ref "R33") (pin "1") (pinfunction "1_1") (pintype "passive"))
      (node (ref "R34") (pin "2") (pinfunction "2_2") (pintype "passive"))
      (node (ref "U9") (pin "10") (pinfunction "5_10") (pintype "bidirectional"))
      (node (ref "U9") (pin "5") (pinfunction "5_5") (pintype "bidirectional"))
      (node (ref "U9") (pin "6") (pinfunction "5_6") (pintype "bidirectional"))
      (node (ref "U9") (pin "7") (pinfunction "5_7") (pintype "bidirectional"))
      (node (ref "U9") (pin "8") (pinfunction "5_8") (pintype "bidirectional"))
      (node (ref "U9") (pin "9") (pinfunction "5_9") (pintype "bidirectional"))
      (node (ref "X5") (pin "2") (pinfunction "S_2") (pintype "passive"))
    )
    (net (code "53") (name "RXLED{slash}SS") (class "Default")
      (node (ref "R6") (pin "1") (pinfunction "1_1") (pintype "passive"))
      (node (ref "U1") (pin "8") (pinfunction "(SS/PCINT0)PB0_8") (pintype "bidirectional"))
    )
    (net (code "54") (name "SCK") (class "Default")
      (node (ref "J4") (pin "3") (pinfunction "3_3") (pintype "passive"))
      (node (ref "U1") (pin "9") (pinfunction "(SCLK/PCINT1)PB1_9") (pintype "bidirectional"))
    )
    (net (code "55") (name "VIN") (class "Default")
      (node (ref "R4") (pin "2") (pinfunction "2_2") (pintype "passive"))
      (node (ref "T1") (pin "3") (pinfunction "G_3") (pintype "passive"))
      (node (ref "T2") (pin "1") (pinfunction "D_1") (pintype "passive"))
    )
    (net (code "56") (name "VUSB") (class "Default")
      (node (ref "C11") (pin "1") (pinfunction "1_1") (pintype "passive"))
      (node (ref "F1") (pin "2") (pinfunction "2_2") (pintype "passive"))
      (node (ref "R11") (pin "2") (pinfunction "2_2") (pintype "passive"))
      (node (ref "T1") (pin "1") (pinfunction "D_1") (pintype "passive"))
      (node (ref "U1") (pin "7") (pinfunction "VBUS_7") (pintype "input"))
      (node (ref "X7") (pin "VBUS") (pinfunction "VBUS_VBUS") (pintype "power_in"))
    )
    (net (code "57") (name "V_HIGH") (class "Default")
      (node (ref "C17") (pin "1") (pinfunction "1_1") (pintype "passive"))
      (node (ref "C9") (pin "1") (pinfunction "1_1") (pintype "passive"))
      (node (ref "J6") (pin "2") (pinfunction "2_2") (pintype "passive"))
      (node (ref "X2") (pin "1") (pinfunction "S_1") (pintype "passive"))
      (node (ref "X3") (pin "1") (pinfunction "S_1") (pintype "passive"))
      (node (ref "X4") (pin "1") (pinfunction "S_1") (pintype "passive"))
      (node (ref "X5") (pin "1") (pinfunction "S_1") (pintype "passive"))
    )
    (net (code "58") (name "unconnected-(X7-PadID)") (class "Default")
      (node (ref "X7") (pin "ID") (pinfunction "ID_ID") (pintype "bidirectional"))
    )
  )
)
